# TestResitorArraySmd.net
KiCad netlist of a schematic drawn in EAGLE
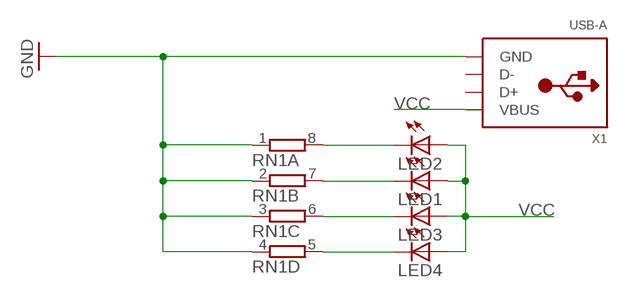
[diagram p0: schematic, sheet 1]

(export (version "E")
  (design (tool "Eeschema 10.0.6"))
  (components
    (comp (ref "LED1")
      (value "LEDSMT1206")
      (footprint "eagle-import:1206")
      (libsource (lib "eagle-import") (part "LEDSMT1206"))
    )
    (comp (ref "LED2")
      (value "LEDSMT1206")
      (footprint "eagle-import:1206")
      (libsource (lib "eagle-import") (part "LEDSMT1206"))
    )
    (comp (ref "LED3")
      (value "LEDSMT1206")
      (footprint "eagle-import:1206")
      (libsource (lib "eagle-import") (part "LEDSMT1206"))
    )
    (comp (ref "LED4")
      (value "LEDSMT1206")
      (footprint "eagle-import:1206")
      (libsource (lib "eagle-import") (part "LEDSMT1206"))
    )
    (comp (ref "RN1")
      (value "4R-NCAT16")
      (footprint "eagle-import:CAT16")
      (libsource (lib "eagle-import") (part "4R-NCAT16"))
    )
    (comp (ref "X1")
      (value "USB-A")
      (footprint "eagle-import:MOLEX_480371000")
      (libsource (lib "eagle-import") (part "USB-A"))
    )
  )
  (nets
    (net (code "1") (name "/VCC") (class "Default")
      (node (ref "LED1") (pin "A") (pinfunction "A_A") (pintype "passive"))
      (node (ref "LED2") (pin "A") (pinfunction "A_A") (pintype "passive"))
      (node (ref "LED3") (pin "A") (pinfunction "A_A") (pintype "passive"))
      (node (ref "LED4") (pin "A") (pinfunction "A_A") (pintype "passive"))
      (node (ref "X1") (pin "1") (pinfunction "VBUS_1") (pintype "power_in"))
    )
    (net (code "2") (name "GND") (class "Default")
      (node (ref "RN1") (pin "1") (pinfunction "1_1") (pintype "passive"))
      (node (ref "RN1") (pin "2") (pinfunction "1_2") (pintype "passive"))
      (node (ref "RN1") (pin "3") (pinfunction "1_3") (pintype "passive"))
      (node (ref "RN1") (pin "4") (pinfunction "1_4") (pintype "passive"))
      (node (ref "X1") (pin "4") (pinfunction "GND_4") (pintype "power_in"))
    )
    (net (code "3") (name "Net-(RN1A-2)") (class "Default")
      (node (ref "LED2") (pin "C") (pinfunction "C_C") (pintype "passive"))
      (node (ref "RN1") (pin "8") (pinfunction "2_8") (pintype "passive"))
    )
    (net (code "4") (name "Net-(RN1B-2)") (class "Default")
      (node (ref "LED1") (pin "C") (pinfunction "C_C") (pintype "passive"))
      (node (ref "RN1") (pin "7") (pinfunction "2_7") (pintype "passive"))
    )
    (net (code "5") (name "Net-(RN1C-2)") (class "Default")
      (node (ref "LED3") (pin "C") (pinfunction "C_C") (pintype "passive"))
      (node (ref "RN1") (pin "6") (pinfunction "2_6") (pintype "passive"))
    )
    (net (code "6") (name "Net-(RN1D-2)") (class "Default")
      (node (ref "LED4") (pin "C") (pinfunction "C_C") (pintype "passive"))
      (node (ref "RN1") (pin "5") (pinfunction "2_5") (pintype "passive"))
    )
    (net (code "7") (name "unconnected-(X1-D+-Pad3)") (class "Default")
      (node (ref "X1") (pin "3") (pinfunction "D+_3") (pintype "bidirectional"))
    )
    (net (code "8") (name "unconnected-(X1-D--Pad2)") (class "Default")
      (node (ref "X1") (pin "2") (pinfunction "D-_2") (pintype "bidirectional"))
    )
  )
)
